# ULN2003_Drv.net
KiCad netlist of a schematic drawn in Altium Designer
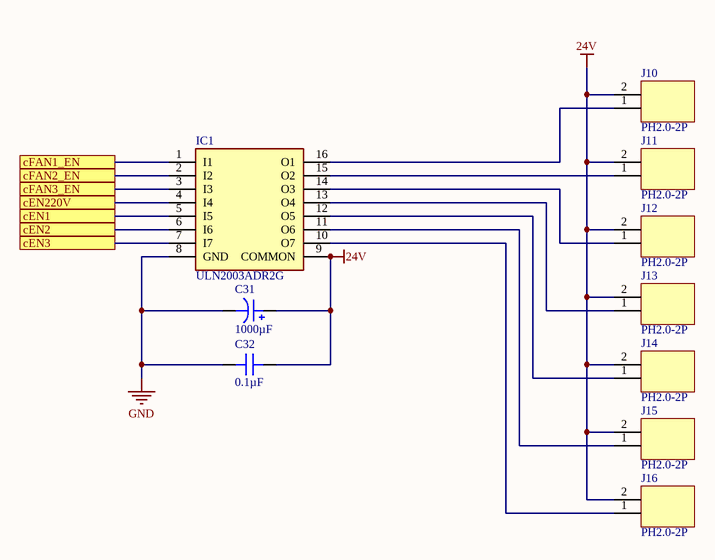
[diagram p0: ULN2003_Drv.SchDoc]

(export (version "E")
  (design (tool "Eeschema 10.0.6"))
  (components
    (comp (ref "C31")
      (value "1000µF")
      (footprint "CAP TH ALUM ELEC D22.00mm S10.00mm H27.00mm")
      (description "CAP ALUM 1000UF 20% 35V SNAP IN")
      (fields (field (name "PART NUMBER") "LKG1V102MESZCK") (field (name "MANUFACTURER") "Nichicon"))
      (libsource (lib "Celestial Altium Library - altium_library") (part "Polarised Capacitor"))
    )
    (comp (ref "C32")
      (value "0.1µF")
      (footprint "CAP 0805_2012")
      (description "CAP CER 0.1UF 50V X7R 0805")
      (fields (field (name "PART NUMBER") "CC0805MRX7R9BB104") (field (name "MANUFACTURER") "Yageo"))
      (libsource (lib "Celestial Altium Library - altium_library") (part "Capacitor"))
    )
    (comp (ref "IC1")
      (value "ULN2003ADR2G")
      (footprint "SamacSys:SOIC127P600X175-16N")
      (description "Integrated Circuit")
      (fields (field (name "MOUSER PART NUMBER") "863-ULN2003ADR2G"))
      (libsource (lib "*") (part "ULN2003ADR2G"))
    )
    (comp (ref "J10") (value "PH2.0-2P") (footprint "PH2.0-2P") (libsource (lib "PH") (part "PH2.0-2P")))
    (comp (ref "J11") (value "PH2.0-2P") (footprint "PH2.0-2P") (libsource (lib "PH") (part "PH2.0-2P")))
    (comp (ref "J12") (value "PH2.0-2P") (footprint "PH2.0-2P") (libsource (lib "PH") (part "PH2.0-2P")))
    (comp (ref "J13") (value "PH2.0-2P") (footprint "PH2.0-2P") (libsource (lib "PH") (part "PH2.0-2P")))
    (comp (ref "J14") (value "PH2.0-2P") (footprint "PH2.0-2P") (libsource (lib "PH") (part "PH2.0-2P")))
    (comp (ref "J15") (value "PH2.0-2P") (footprint "PH2.0-2P") (libsource (lib "PH") (part "PH2.0-2P")))
    (comp (ref "J16") (value "PH2.0-2P") (footprint "PH2.0-2P") (libsource (lib "PH") (part "PH2.0-2P")))
  )
  (nets
    (net (code "1") (name "/cEN1") (class "Default")
      (node (ref "IC1") (pin "5") (pinfunction "I5_5") (pintype "passive"))
    )
    (net (code "2") (name "/cEN2") (class "Default")
      (node (ref "IC1") (pin "6") (pinfunction "I6_6") (pintype "passive"))
    )
    (net (code "3") (name "/cEN3") (class "Default")
      (node (ref "IC1") (pin "7") (pinfunction "I7_7") (pintype "passive"))
    )
    (net (code "4") (name "/cEN220V") (class "Default")
      (node (ref "IC1") (pin "4") (pinfunction "I4_4") (pintype "passive"))
    )
    (net (code "5") (name "/cFAN1_EN") (class "Default")
      (node (ref "IC1") (pin "1") (pinfunction "I1_1") (pintype "passive"))
    )
    (net (code "6") (name "/cFAN2_EN") (class "Default")
      (node (ref "IC1") (pin "2") (pinfunction "I2_2") (pintype "passive"))
    )
    (net (code "7") (name "/cFAN3_EN") (class "Default")
      (node (ref "IC1") (pin "3") (pinfunction "I3_3") (pintype "passive"))
    )
    (net (code "8") (name "24V") (class "Default")
      (node (ref "C31") (pin "1") (pinfunction "1_1") (pintype "passive"))
      (node (ref "C32") (pin "1") (pinfunction "1_1") (pintype "passive"))
      (node (ref "IC1") (pin "9") (pinfunction "COMMON_9") (pintype "passive"))
      (node (ref "J10") (pin "2") (pinfunction "2_2") (pintype "passive"))
      (node (ref "J11") (pin "2") (pinfunction "2_2") (pintype "passive"))
      (node (ref "J12") (pin "2") (pinfunction "2_2") (pintype "passive"))
      (node (ref "J13") (pin "2") (pinfunction "2_2") (pintype "passive"))
      (node (ref "J14") (pin "2") (pinfunction "2_2") (pintype "passive"))
      (node (ref "J15") (pin "2") (pinfunction "2_2") (pintype "passive"))
      (node (ref "J16") (pin "2") (pinfunction "2_2") (pintype "passive"))
    )
    (net (code "9") (name "GND") (class "Default")
      (node (ref "C31") (pin "2") (pinfunction "2_2") (pintype "passive"))
      (node (ref "C32") (pin "2") (pinfunction "2_2") (pintype "passive"))
      (node (ref "IC1") (pin "8") (pinfunction "GND_8") (pintype "passive"))
    )
    (net (code "10") (name "Net-(IC1-O1)") (class "Default")
      (node (ref "IC1") (pin "16") (pinfunction "O1_16") (pintype "passive"))
      (node (ref "J10") (pin "1") (pinfunction "1_1") (pintype "passive"))
    )
    (net (code "11") (name "Net-(IC1-O2)") (class "Default")
      (node (ref "IC1") (pin "15") (pinfunction "O2_15") (pintype "passive"))
      (node (ref "J11") (pin "1") (pinfunction "1_1") (pintype "passive"))
    )
    (net (code "12") (name "Net-(IC1-O3)") (class "Default")
      (node (ref "IC1") (pin "14") (pinfunction "O3_14") (pintype "passive"))
      (node (ref "J12") (pin "1") (pinfunction "1_1") (pintype "passive"))
    )
    (net (code "13") (name "Net-(IC1-O4)") (class "Default")
      (node (ref "IC1") (pin "13") (pinfunction "O4_13") (pintype "passive"))
      (node (ref "J13") (pin "1") (pinfunction "1_1") (pintype "passive"))
    )
    (net (code "14") (name "Net-(IC1-O5)") (class "Default")
      (node (ref "IC1") (pin "12") (pinfunction "O5_12") (pintype "passive"))
      (node (ref "J14") (pin "1") (pinfunction "1_1") (pintype "passive"))
    )
    (net (code "15") (name "Net-(IC1-O6)") (class "Default")
      (node (ref "IC1") (pin "11") (pinfunction "O6_11") (pintype "passive"))
      (node (ref "J15") (pin "1") (pinfunction "1_1") (pintype "passive"))
    )
    (net (code "16") (name "Net-(IC1-O7)") (class "Default")
      (node (ref "IC1") (pin "10") (pinfunction "O7_10") (pintype "passive"))
      (node (ref "J16") (pin "1") (pinfunction "1_1") (pintype "passive"))
    )
  )
)
